# MPPT_charger.net
KiCad netlist of a schematic drawn in Altium Designer
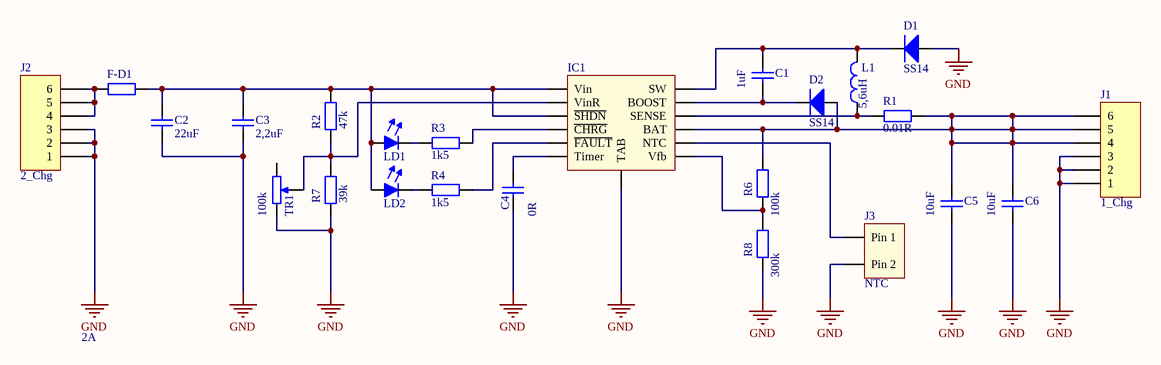
[diagram p0: MPPT charger.SchDoc]

(export (version "E")
  (design (tool "Eeschema 10.0.6"))
  (components
    (comp (ref "C1")
      (value "1uF")
      (footprint "0805 CAP")
      (description "Capacitor")
      (fields (field (name "VOLTAGE") "35V"))
      (libsource (lib "IKSOR_LIB_main") (part "Capacitor NP"))
    )
    (comp (ref "C2")
      (value "22uF")
      (footprint "2512 CAP")
      (description "Capacitor")
      (fields (field (name "VOLTAGE") "35V"))
      (libsource (lib "IKSOR_LIB_main") (part "Capacitor NP"))
    )
    (comp (ref "C3")
      (value "2,2uF")
      (footprint "1206 CAP")
      (description "Capacitor")
      (fields (field (name "VOLTAGE") "35V"))
      (libsource (lib "IKSOR_LIB_main") (part "Capacitor NP"))
    )
    (comp (ref "C4")
      (value "0R")
      (footprint "0603 cap")
      (description "Capacitor/Bridge")
      (libsource (lib "IKSOR_LIB_main") (part "Capacitor NP"))
    )
    (comp (ref "C5")
      (value "10uF")
      (footprint "0805 CAP")
      (description "Capacitor")
      (fields (field (name "VOLTAGE") "6V"))
      (libsource (lib "IKSOR_LIB_main") (part "Capacitor NP"))
    )
    (comp (ref "C6")
      (value "10uF")
      (footprint "1812 CAP")
      (description "Capacitor")
      (fields (field (name "VOLTAGE") "6V"))
      (libsource (lib "IKSOR_LIB_main") (part "Capacitor NP"))
    )
    (comp (ref "D1")
      (value "SS14")
      (footprint "SMB")
      (description "High Conductance Fast Diode")
      (libsource (lib "VolkD3D") (part "Diode 1N4148"))
    )
    (comp (ref "D2")
      (value "SS14")
      (footprint "SMB")
      (description "High Conductance Fast Diode")
      (libsource (lib "VolkD3D") (part "Diode 1N4148"))
    )
    (comp (ref "F-D1")
      (value "2A")
      (footprint "1206 RES")
      (description "Resistor SMD")
      (fields (field (name "Comment") "Resistor generic"))
      (libsource (lib "IKSOR_LIB_main") (part "Resistor"))
    )
    (comp (ref "IC1")
      (value "LTC3652")
      (footprint "MSOP12 - EP")
      (libsource (lib "IKSOR_LIB_main") (part "LTC3652"))
    )
    (comp (ref "J1")
      (value "1_Chg")
      (footprint "HDR1X6")
      (description "Header, 6-Pin")
      (fields (field (name "PUBLISHER") "Altium Limited"))
      (libsource (lib "") (part "Header 6_1"))
    )
    (comp (ref "J2")
      (value "2_Chg")
      (footprint "HDR1X6")
      (description "Header, 6-Pin")
      (fields (field (name "PUBLISHER") "Altium Limited"))
      (libsource (lib "Miscellaneous Connectors") (part "Header 6"))
    )
    (comp (ref "J3")
      (value "NTC")
      (footprint "HDR1X2")
      (libsource (lib "IKSOR_LIB_main") (part "Pin Header 2"))
    )
    (comp (ref "L1")
      (value "5,6uH")
      (footprint "FDSD0420-H")
      (description "Single coil")
      (fields (field (name "Comment") "Inductor"))
      (libsource (lib "IKSOR_LIB_main") (part "Inductor"))
    )
    (comp (ref "LD1")
      (value "LED diode")
      (footprint "LED_0603")
      (description "LED")
      (libsource (lib "IKSOR_LIB_main") (part "LED diode"))
    )
    (comp (ref "LD2")
      (value "LED diode")
      (footprint "LED_0603")
      (description "LED")
      (libsource (lib "IKSOR_LIB_main") (part "LED diode"))
    )
    (comp (ref "R1")
      (value "0.01R")
      (footprint "1812 RES")
      (description "Resistor SMD")
      (fields (field (name "Comment") "Resistor generic"))
      (libsource (lib "IKSOR_LIB_main") (part "Resistor"))
    )
    (comp (ref "R2")
      (value "47k")
      (footprint "0603 RES")
      (description "Resistor SMD")
      (fields (field (name "Comment") "Resistor generic"))
      (libsource (lib "IKSOR_LIB_main") (part "Resistor"))
    )
    (comp (ref "R3")
      (value "1k5")
      (footprint "0603 RES")
      (description "Resistor SMD")
      (fields (field (name "Comment") "Resistor generic"))
      (libsource (lib "IKSOR_LIB_main") (part "Resistor"))
    )
    (comp (ref "R4")
      (value "1k5")
      (footprint "0603 RES")
      (description "Resistor SMD")
      (fields (field (name "Comment") "Resistor generic"))
      (libsource (lib "IKSOR_LIB_main") (part "Resistor"))
    )
    (comp (ref "R6")
      (value "100k")
      (footprint "0603 RES")
      (description "Resistor SMD")
      (fields (field (name "Comment") "FB1"))
      (libsource (lib "IKSOR_LIB_main") (part "Resistor"))
    )
    (comp (ref "R7")
      (value "39k")
      (footprint "0603 RES")
      (description "Resistor SMD")
      (fields (field (name "Comment") "Resistor generic"))
      (libsource (lib "IKSOR_LIB_main") (part "Resistor"))
    )
    (comp (ref "R8")
      (value "300k")
      (footprint "0603 RES")
      (description "Resistor SMD")
      (fields (field (name "Comment") "FB2"))
      (libsource (lib "IKSOR_LIB_main") (part "Resistor"))
    )
    (comp (ref "TR1")
      (value "100k")
      (footprint "Multiturn 1")
      (description "Trimmer")
      (fields (field (name "Comment") "Resistor_trim"))
      (libsource (lib "IKSOR_LIB_main") (part "Resistor_trim"))
    )
  )
  (nets
    (net (code "1") (name "GND") (class "Default")
      (node (ref "C2") (pin "1") (pinfunction "1_1") (pintype "passive"))
      (node (ref "C3") (pin "1") (pinfunction "1_1") (pintype "passive"))
      (node (ref "C4") (pin "1") (pinfunction "1_1") (pintype "passive"))
      (node (ref "C5") (pin "1") (pinfunction "1_1") (pintype "passive"))
      (node (ref "C6") (pin "1") (pinfunction "1_1") (pintype "passive"))
      (node (ref "D1") (pin "1") (pinfunction "A_1") (pintype "passive"))
      (node (ref "IC1") (pin "13") (pinfunction "TAB_13") (pintype "passive"))
      (node (ref "J1") (pin "1") (pinfunction "1_1") (pintype "passive"))
      (node (ref "J1") (pin "2") (pinfunction "2_2") (pintype "passive"))
      (node (ref "J1") (pin "3") (pinfunction "3_3") (pintype "passive"))
      (node (ref "J2") (pin "1") (pinfunction "1_1") (pintype "passive"))
      (node (ref "J2") (pin "2") (pinfunction "2_2") (pintype "passive"))
      (node (ref "J2") (pin "3") (pinfunction "3_3") (pintype "passive"))
      (node (ref "J3") (pin "2") (pinfunction "Pin_2_2") (pintype "passive"))
      (node (ref "R7") (pin "1") (pinfunction "1_1") (pintype "passive"))
      (node (ref "R8") (pin "1") (pinfunction "1_1") (pintype "passive"))
      (node (ref "TR1") (pin "2") (pinfunction "BOT_2") (pintype "passive"))
    )
    (net (code "2") (name "Net-(D1-K)") (class "Default")
      (node (ref "C1") (pin "2") (pinfunction "2_2") (pintype "passive"))
      (node (ref "D1") (pin "2") (pinfunction "K_2") (pintype "passive"))
      (node (ref "IC1") (pin "12") (pinfunction "SW_12") (pintype "passive"))
      (node (ref "L1") (pin "2") (pinfunction "2_2") (pintype "passive"))
    )
    (net (code "3") (name "Net-(D2-A)") (class "Default")
      (node (ref "C5") (pin "2") (pinfunction "2_2") (pintype "passive"))
      (node (ref "C6") (pin "2") (pinfunction "2_2") (pintype "passive"))
      (node (ref "D2") (pin "1") (pinfunction "A_1") (pintype "passive"))
      (node (ref "IC1") (pin "9") (pinfunction "BAT_9") (pintype "passive"))
      (node (ref "J1") (pin "4") (pinfunction "4_4") (pintype "passive"))
      (node (ref "J1") (pin "5") (pinfunction "5_5") (pintype "passive"))
      (node (ref "J1") (pin "6") (pinfunction "6_6") (pintype "passive"))
      (node (ref "R1") (pin "1") (pinfunction "1_1") (pintype "passive"))
      (node (ref "R6") (pin "2") (pinfunction "2_2") (pintype "passive"))
    )
    (net (code "4") (name "Net-(D2-K)") (class "Default")
      (node (ref "C1") (pin "1") (pinfunction "1_1") (pintype "passive"))
      (node (ref "D2") (pin "2") (pinfunction "K_2") (pintype "passive"))
      (node (ref "IC1") (pin "11") (pinfunction "BOOST_11") (pintype "passive"))
    )
    (net (code "5") (name "Net-(F-D1-Pad1)") (class "Default")
      (node (ref "F-D1") (pin "1") (pinfunction "1_1") (pintype "passive"))
      (node (ref "J2") (pin "4") (pinfunction "4_4") (pintype "passive"))
      (node (ref "J2") (pin "5") (pinfunction "5_5") (pintype "passive"))
      (node (ref "J2") (pin "6") (pinfunction "6_6") (pintype "passive"))
    )
    (net (code "6") (name "Net-(IC1-NTC)") (class "Default")
      (node (ref "IC1") (pin "8") (pinfunction "NTC_8") (pintype "passive"))
      (node (ref "J3") (pin "1") (pinfunction "Pin_1_1") (pintype "passive"))
    )
    (net (code "7") (name "Net-(IC1-SENSE)") (class "Default")
      (node (ref "IC1") (pin "10") (pinfunction "SENSE_10") (pintype "passive"))
      (node (ref "L1") (pin "1") (pinfunction "1_1") (pintype "passive"))
      (node (ref "R1") (pin "2") (pinfunction "2_2") (pintype "passive"))
    )
    (net (code "8") (name "Net-(IC1-Timer)") (class "Default")
      (node (ref "C4") (pin "2") (pinfunction "2_2") (pintype "passive"))
      (node (ref "IC1") (pin "6") (pinfunction "Timer_6") (pintype "passive"))
    )
    (net (code "9") (name "Net-(IC1-Vfb)") (class "Default")
      (node (ref "IC1") (pin "7") (pinfunction "Vfb_7") (pintype "passive"))
      (node (ref "R6") (pin "1") (pinfunction "1_1") (pintype "passive"))
      (node (ref "R8") (pin "2") (pinfunction "2_2") (pintype "passive"))
    )
    (net (code "10") (name "Net-(IC1-Vin)") (class "Default")
      (node (ref "C2") (pin "2") (pinfunction "2_2") (pintype "passive"))
      (node (ref "C3") (pin "2") (pinfunction "2_2") (pintype "passive"))
      (node (ref "F-D1") (pin "2") (pinfunction "2_2") (pintype "passive"))
      (node (ref "IC1") (pin "1") (pinfunction "Vin_1") (pintype "passive"))
      (node (ref "IC1") (pin "3") (pinfunction "~{SHDN}_3") (pintype "passive"))
      (node (ref "LD1") (pin "1") (pinfunction "A1_1") (pintype "passive"))
      (node (ref "LD2") (pin "1") (pinfunction "A1_1") (pintype "passive"))
      (node (ref "R2") (pin "2") (pinfunction "2_2") (pintype "passive"))
    )
    (net (code "11") (name "Net-(IC1-VinR)") (class "Default")
      (node (ref "IC1") (pin "2") (pinfunction "VinR_2") (pintype "passive"))
      (node (ref "R2") (pin "1") (pinfunction "1_1") (pintype "passive"))
      (node (ref "R7") (pin "2") (pinfunction "2_2") (pintype "passive"))
      (node (ref "TR1") (pin "3") (pinfunction "TAP_3") (pintype "passive"))
    )
    (net (code "12") (name "Net-(IC1-~{CHRG})") (class "Default")
      (node (ref "IC1") (pin "4") (pinfunction "~{CHRG}_4") (pintype "passive"))
      (node (ref "R3") (pin "2") (pinfunction "2_2") (pintype "passive"))
    )
    (net (code "13") (name "Net-(IC1-~{FAULT})") (class "Default")
      (node (ref "IC1") (pin "5") (pinfunction "~{FAULT}_5") (pintype "passive"))
      (node (ref "R4") (pin "2") (pinfunction "2_2") (pintype "passive"))
    )
    (net (code "14") (name "Net-(LD1-K)") (class "Default")
      (node (ref "LD1") (pin "2") (pinfunction "K_2") (pintype "passive"))
      (node (ref "R3") (pin "1") (pinfunction "1_1") (pintype "passive"))
    )
    (net (code "15") (name "Net-(LD2-K)") (class "Default")
      (node (ref "LD2") (pin "2") (pinfunction "K_2") (pintype "passive"))
      (node (ref "R4") (pin "1") (pinfunction "1_1") (pintype "passive"))
    )
    (net (code "16") (name "unconnected-(TR1-TOP-Pad1)") (class "Default")
      (node (ref "TR1") (pin "1") (pinfunction "TOP_1") (pintype "passive"))
    )
  )
)
